# v1.net
KiCad netlist of a schematic drawn in EAGLE
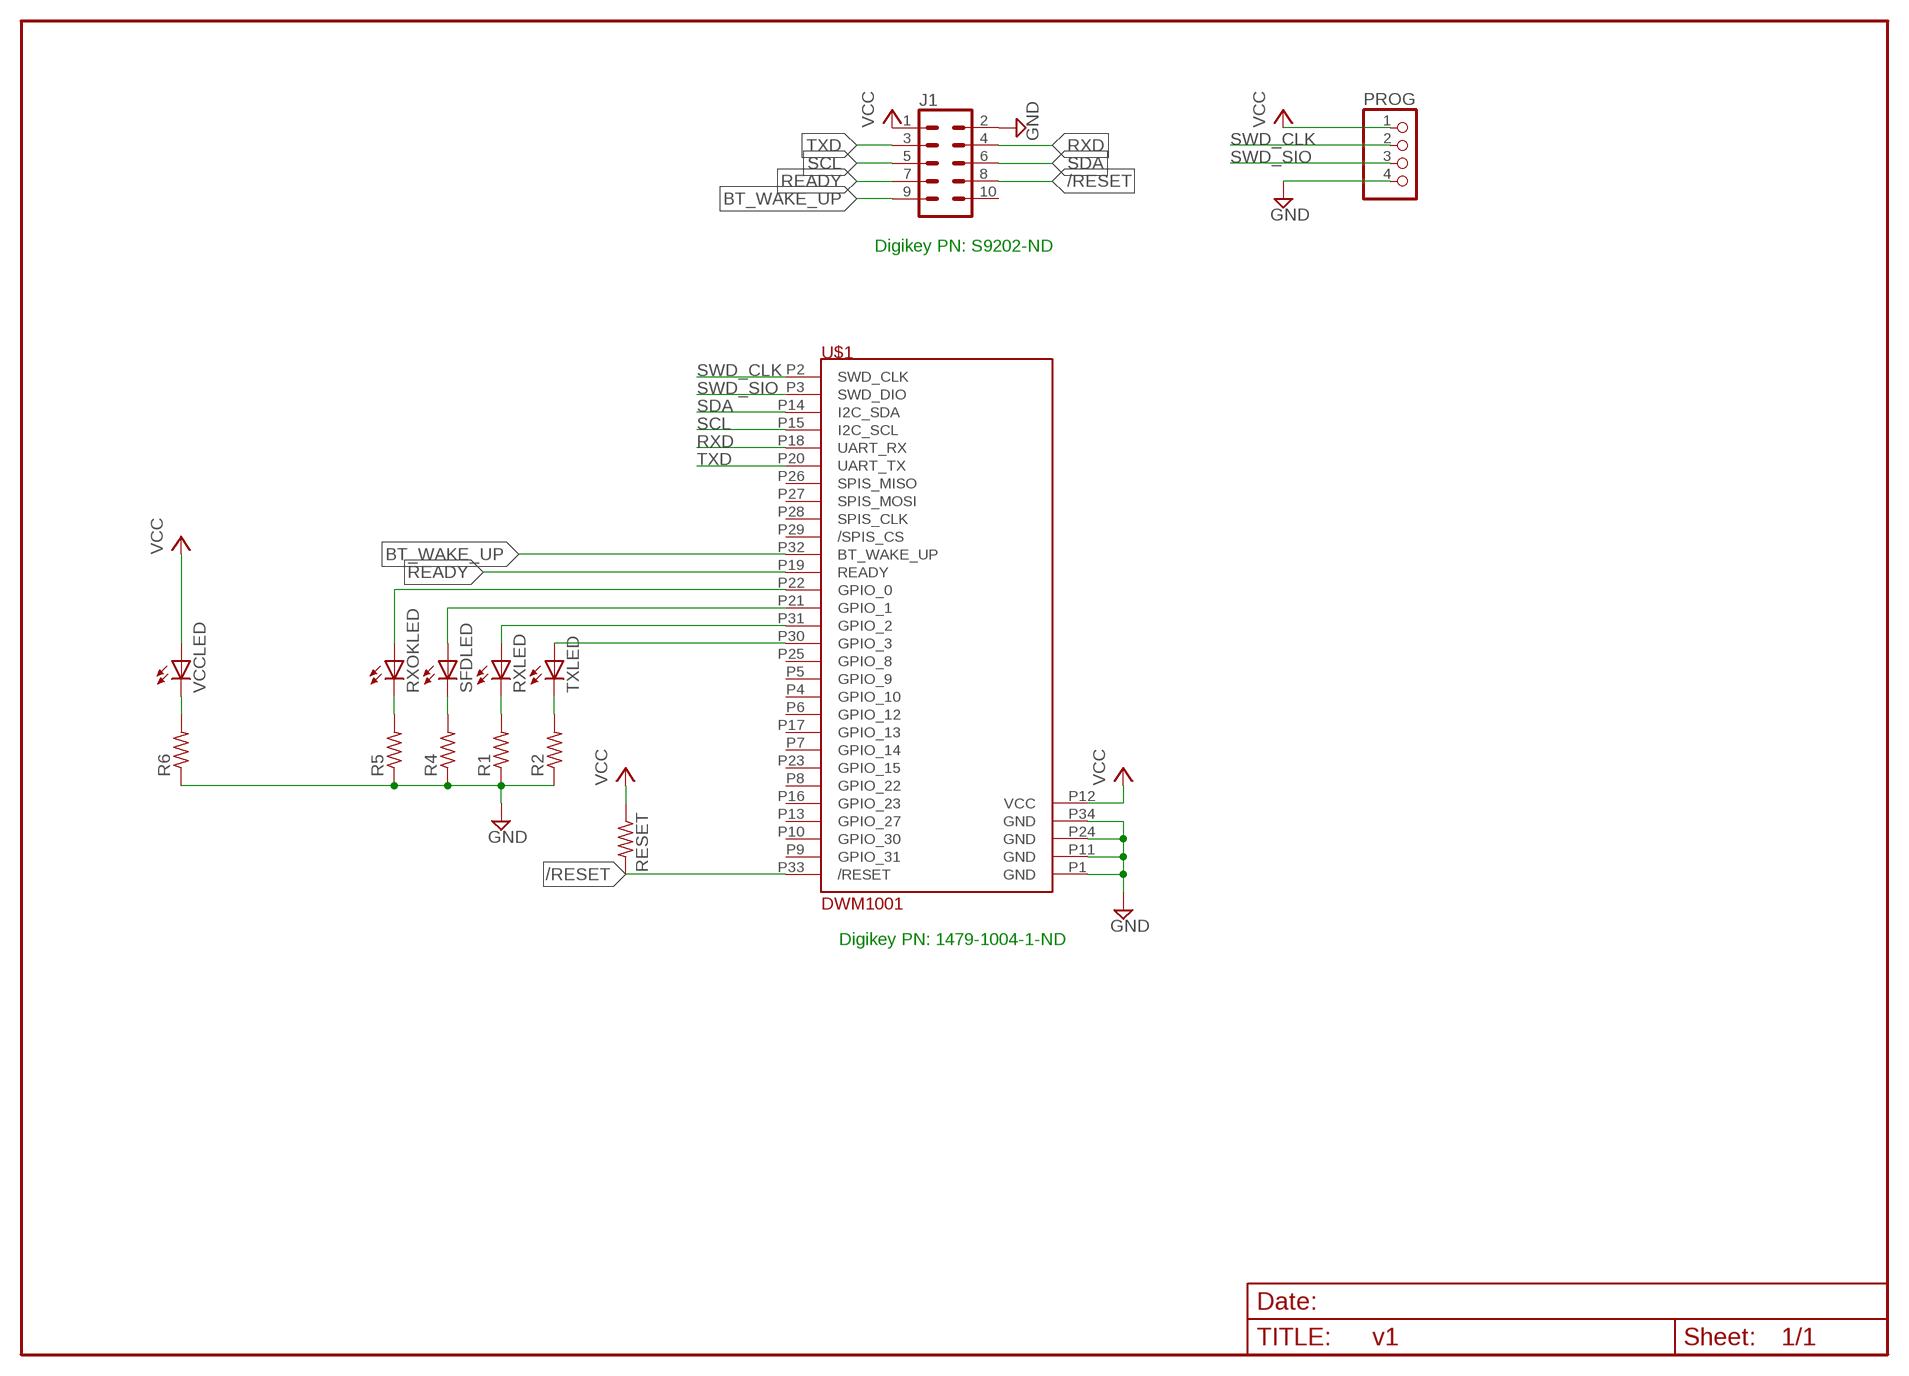
[diagram p0: schematic, sheet 1]

(export (version "E")
  (design (tool "Eeschema 10.0.6"))
  (components
    (comp (ref "J1")
      (value "CONN_05X2RAF")
      (footprint "eagle-import:2X5-RAF")
      (libsource (lib "eagle-import") (part "CONN_05X2RAF"))
    )
    (comp (ref "PROG")
      (value "PINHD-1X4")
      (footprint "eagle-import:1X04")
      (libsource (lib "eagle-import") (part "PINHD-1X4"))
    )
    (comp (ref "R1")
      (value "R-US_R0603")
      (footprint "eagle-import:R0603")
      (libsource (lib "eagle-import") (part "R-US_R0603"))
    )
    (comp (ref "R2")
      (value "R-US_R0603")
      (footprint "eagle-import:R0603")
      (libsource (lib "eagle-import") (part "R-US_R0603"))
    )
    (comp (ref "R4")
      (value "R-US_R0603")
      (footprint "eagle-import:R0603")
      (libsource (lib "eagle-import") (part "R-US_R0603"))
    )
    (comp (ref "R5")
      (value "R-US_R0603")
      (footprint "eagle-import:R0603")
      (libsource (lib "eagle-import") (part "R-US_R0603"))
    )
    (comp (ref "R6")
      (value "R-US_R0603")
      (footprint "eagle-import:R0603")
      (libsource (lib "eagle-import") (part "R-US_R0603"))
    )
    (comp (ref "RESET")
      (value "R-US_R0603")
      (footprint "eagle-import:R0603")
      (libsource (lib "eagle-import") (part "R-US_R0603"))
    )
    (comp (ref "RXLED")
      (value "LEDCHIPLED_0603")
      (footprint "eagle-import:CHIPLED_0603")
      (libsource (lib "eagle-import") (part "LEDCHIPLED_0603"))
    )
    (comp (ref "RXOKLED")
      (value "LEDCHIPLED_0603")
      (footprint "eagle-import:CHIPLED_0603")
      (libsource (lib "eagle-import") (part "LEDCHIPLED_0603"))
    )
    (comp (ref "SFDLED")
      (value "LEDCHIPLED_0603")
      (footprint "eagle-import:CHIPLED_0603")
      (libsource (lib "eagle-import") (part "LEDCHIPLED_0603"))
    )
    (comp (ref "TXLED")
      (value "LEDCHIPLED_0603")
      (footprint "eagle-import:CHIPLED_0603")
      (libsource (lib "eagle-import") (part "LEDCHIPLED_0603"))
    )
    (comp (ref "U$1")
      (value "DWM1001")
      (footprint "eagle-import:DWM1001_LAND_PATTERN")
      (libsource (lib "eagle-import") (part "DWM1001"))
    )
    (comp (ref "VCCLED")
      (value "LEDCHIPLED_0603")
      (footprint "eagle-import:CHIPLED_0603")
      (libsource (lib "eagle-import") (part "LEDCHIPLED_0603"))
    )
  )
  (nets
    (net (code "1") (name "/SWD_CLK") (class "Default")
      (node (ref "PROG") (pin "2") (pinfunction "2_2") (pintype "passive"))
      (node (ref "U$1") (pin "P2") (pinfunction "SWD_CLK_P2") (pintype "bidirectional"))
    )
    (net (code "2") (name "/SWD_SIO") (class "Default")
      (node (ref "PROG") (pin "3") (pinfunction "3_3") (pintype "passive"))
      (node (ref "U$1") (pin "P3") (pinfunction "SWD_DIO_P3") (pintype "bidirectional"))
    )
    (net (code "3") (name "BT_WAKE_UP") (class "Default")
      (node (ref "J1") (pin "9") (pinfunction "9_9") (pintype "passive"))
      (node (ref "U$1") (pin "P32") (pinfunction "BT_WAKE_UP_P32") (pintype "bidirectional"))
    )
    (net (code "4") (name "GND") (class "Default")
      (node (ref "J1") (pin "2") (pinfunction "2_2") (pintype "passive"))
      (node (ref "PROG") (pin "4") (pinfunction "4_4") (pintype "passive"))
      (node (ref "R1") (pin "1") (pinfunction "1_1") (pintype "passive"))
      (node (ref "R2") (pin "1") (pinfunction "1_1") (pintype "passive"))
      (node (ref "R4") (pin "1") (pinfunction "1_1") (pintype "passive"))
      (node (ref "R5") (pin "1") (pinfunction "1_1") (pintype "passive"))
      (node (ref "R6") (pin "1") (pinfunction "1_1") (pintype "passive"))
      (node (ref "U$1") (pin "P1") (pinfunction "GND_P1") (pintype "bidirectional"))
      (node (ref "U$1") (pin "P11") (pinfunction "GND_P11") (pintype "bidirectional"))
      (node (ref "U$1") (pin "P24") (pinfunction "GND_P24") (pintype "bidirectional"))
      (node (ref "U$1") (pin "P34") (pinfunction "GND_P34") (pintype "bidirectional"))
    )
    (net (code "5") (name "Net-(R1-Pad2)") (class "Default")
      (node (ref "R1") (pin "2") (pinfunction "2_2") (pintype "passive"))
      (node (ref "RXLED") (pin "C") (pinfunction "C_C") (pintype "passive"))
    )
    (net (code "6") (name "Net-(R2-Pad2)") (class "Default")
      (node (ref "R2") (pin "2") (pinfunction "2_2") (pintype "passive"))
      (node (ref "TXLED") (pin "C") (pinfunction "C_C") (pintype "passive"))
    )
    (net (code "7") (name "Net-(R4-Pad2)") (class "Default")
      (node (ref "R4") (pin "2") (pinfunction "2_2") (pintype "passive"))
      (node (ref "SFDLED") (pin "C") (pinfunction "C_C") (pintype "passive"))
    )
    (net (code "8") (name "Net-(R5-Pad2)") (class "Default")
      (node (ref "R5") (pin "2") (pinfunction "2_2") (pintype "passive"))
      (node (ref "RXOKLED") (pin "C") (pinfunction "C_C") (pintype "passive"))
    )
    (net (code "9") (name "Net-(R6-Pad2)") (class "Default")
      (node (ref "R6") (pin "2") (pinfunction "2_2") (pintype "passive"))
      (node (ref "VCCLED") (pin "C") (pinfunction "C_C") (pintype "passive"))
    )
    (net (code "10") (name "Net-(U$1-GPIO_0)") (class "Default")
      (node (ref "RXOKLED") (pin "A") (pinfunction "A_A") (pintype "passive"))
      (node (ref "U$1") (pin "P22") (pinfunction "GPIO_0_P22") (pintype "bidirectional"))
    )
    (net (code "11") (name "Net-(U$1-GPIO_1)") (class "Default")
      (node (ref "SFDLED") (pin "A") (pinfunction "A_A") (pintype "passive"))
      (node (ref "U$1") (pin "P21") (pinfunction "GPIO_1_P21") (pintype "bidirectional"))
    )
    (net (code "12") (name "Net-(U$1-GPIO_2)") (class "Default")
      (node (ref "RXLED") (pin "A") (pinfunction "A_A") (pintype "passive"))
      (node (ref "U$1") (pin "P31") (pinfunction "GPIO_2_P31") (pintype "bidirectional"))
    )
    (net (code "13") (name "Net-(U$1-GPIO_3)") (class "Default")
      (node (ref "TXLED") (pin "A") (pinfunction "A_A") (pintype "passive"))
      (node (ref "U$1") (pin "P30") (pinfunction "GPIO_3_P30") (pintype "bidirectional"))
    )
    (net (code "14") (name "READY") (class "Default")
      (node (ref "J1") (pin "7") (pinfunction "7_7") (pintype "passive"))
      (node (ref "U$1") (pin "P19") (pinfunction "READY_P19") (pintype "bidirectional"))
    )
    (net (code "15") (name "RXD") (class "Default")
      (node (ref "J1") (pin "4") (pinfunction "4_4") (pintype "passive"))
      (node (ref "U$1") (pin "P18") (pinfunction "UART_RX_P18") (pintype "bidirectional"))
    )
    (net (code "16") (name "SCL") (class "Default")
      (node (ref "J1") (pin "5") (pinfunction "5_5") (pintype "passive"))
      (node (ref "U$1") (pin "P15") (pinfunction "I2C_SCL_P15") (pintype "bidirectional"))
    )
    (net (code "17") (name "SDA") (class "Default")
      (node (ref "J1") (pin "6") (pinfunction "6_6") (pintype "passive"))
      (node (ref "U$1") (pin "P14") (pinfunction "I2C_SDA_P14") (pintype "bidirectional"))
    )
    (net (code "18") (name "TXD") (class "Default")
      (node (ref "J1") (pin "3") (pinfunction "3_3") (pintype "passive"))
      (node (ref "U$1") (pin "P20") (pinfunction "UART_TX_P20") (pintype "bidirectional"))
    )
    (net (code "19") (name "VCC") (class "Default")
      (node (ref "J1") (pin "1") (pinfunction "1_1") (pintype "passive"))
      (node (ref "PROG") (pin "1") (pinfunction "1_1") (pintype "passive"))
      (node (ref "RESET") (pin "1") (pinfunction "1_1") (pintype "passive"))
      (node (ref "U$1") (pin "P12") (pinfunction "VCC_P12") (pintype "bidirectional"))
      (node (ref "VCCLED") (pin "A") (pinfunction "A_A") (pintype "passive"))
    )
    (net (code "20") (name "unconnected-(J1-Pad10)") (class "Default")
      (node (ref "J1") (pin "10") (pinfunction "10_10") (pintype "passive"))
    )
    (net (code "21") (name "unconnected-(U$1-GPIO_8-PadP25)") (class "Default")
      (node (ref "U$1") (pin "P25") (pinfunction "GPIO_8_P25") (pintype "bidirectional"))
    )
    (net (code "22") (name "unconnected-(U$1-GPIO_9-PadP5)") (class "Default")
      (node (ref "U$1") (pin "P5") (pinfunction "GPIO_9_P5") (pintype "bidirectional"))
    )
    (net (code "23") (name "unconnected-(U$1-GPIO_10-PadP4)") (class "Default")
      (node (ref "U$1") (pin "P4") (pinfunction "GPIO_10_P4") (pintype "bidirectional"))
    )
    (net (code "24") (name "unconnected-(U$1-GPIO_12-PadP6)") (class "Default")
      (node (ref "U$1") (pin "P6") (pinfunction "GPIO_12_P6") (pintype "bidirectional"))
    )
    (net (code "25") (name "unconnected-(U$1-GPIO_13-PadP17)") (class "Default")
      (node (ref "U$1") (pin "P17") (pinfunction "GPIO_13_P17") (pintype "bidirectional"))
    )
    (net (code "26") (name "unconnected-(U$1-GPIO_14-PadP7)") (class "Default")
      (node (ref "U$1") (pin "P7") (pinfunction "GPIO_14_P7") (pintype "bidirectional"))
    )
    (net (code "27") (name "unconnected-(U$1-GPIO_15-PadP23)") (class "Default")
      (node (ref "U$1") (pin "P23") (pinfunction "GPIO_15_P23") (pintype "bidirectional"))
    )
    (net (code "28") (name "unconnected-(U$1-GPIO_22-PadP8)") (class "Default")
      (node (ref "U$1") (pin "P8") (pinfunction "GPIO_22_P8") (pintype "bidirectional"))
    )
    (net (code "29") (name "unconnected-(U$1-GPIO_23-PadP16)") (class "Default")
      (node (ref "U$1") (pin "P16") (pinfunction "GPIO_23_P16") (pintype "bidirectional"))
    )
    (net (code "30") (name "unconnected-(U$1-GPIO_27-PadP13)") (class "Default")
      (node (ref "U$1") (pin "P13") (pinfunction "GPIO_27_P13") (pintype "bidirectional"))
    )
    (net (code "31") (name "unconnected-(U$1-GPIO_30-PadP10)") (class "Default")
      (node (ref "U$1") (pin "P10") (pinfunction "GPIO_30_P10") (pintype "bidirectional"))
    )
    (net (code "32") (name "unconnected-(U$1-GPIO_31-PadP9)") (class "Default")
      (node (ref "U$1") (pin "P9") (pinfunction "GPIO_31_P9") (pintype "bidirectional"))
    )
    (net (code "33") (name "unconnected-(U$1-SPIS_CLK-PadP28)") (class "Default")
      (node (ref "U$1") (pin "P28") (pinfunction "SPIS_CLK_P28") (pintype "bidirectional"))
    )
    (net (code "34") (name "unconnected-(U$1-SPIS_MISO-PadP26)") (class "Default")
      (node (ref "U$1") (pin "P26") (pinfunction "SPIS_MISO_P26") (pintype "bidirectional"))
    )
    (net (code "35") (name "unconnected-(U$1-SPIS_MOSI-PadP27)") (class "Default")
      (node (ref "U$1") (pin "P27") (pinfunction "SPIS_MOSI_P27") (pintype "bidirectional"))
    )
    (net (code "36") (name "unconnected-(U$1-{slash}SPIS_CS-PadP29)") (class "Default")
      (node (ref "U$1") (pin "P29") (pinfunction "/SPIS_CS_P29") (pintype "bidirectional"))
    )
    (net (code "37") (name "{slash}RESET") (class "Default")
      (node (ref "J1") (pin "8") (pinfunction "8_8") (pintype "passive"))
      (node (ref "RESET") (pin "2") (pinfunction "2_2") (pintype "passive"))
      (node (ref "U$1") (pin "P33") (pinfunction "/RESET_P33") (pintype "bidirectional"))
    )
  )
)
